# Shematic.net
KiCad netlist of a schematic drawn in Altium Designer
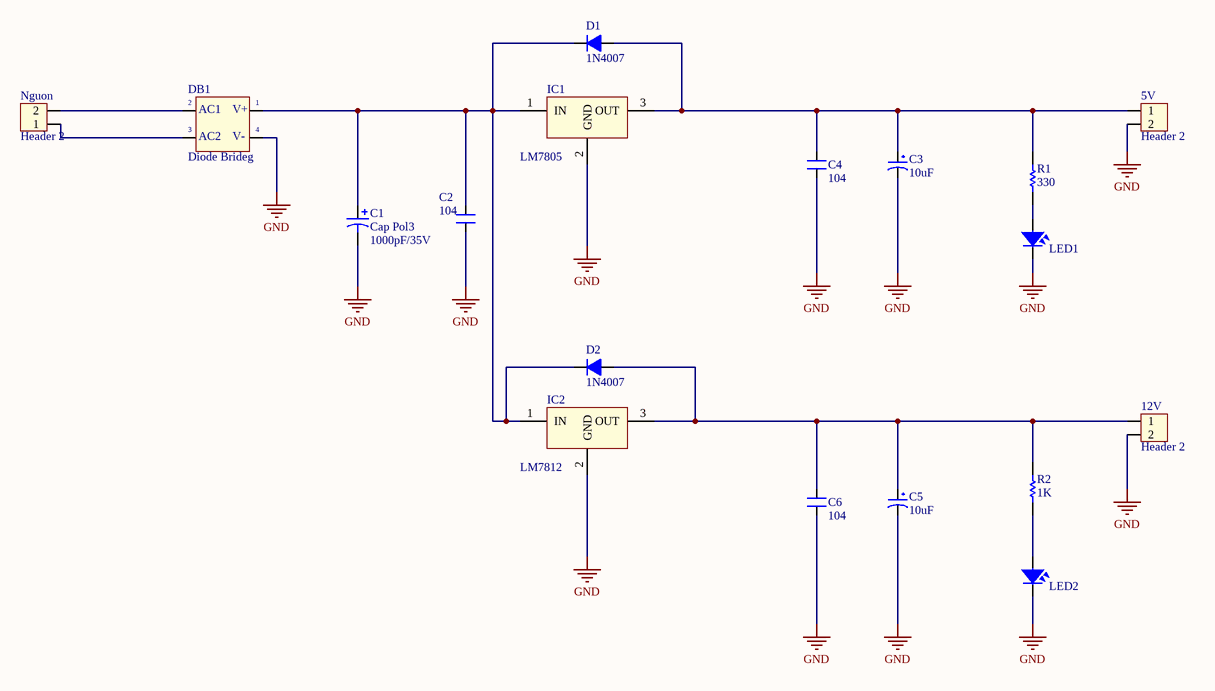
[diagram p0: Shematic.SchDoc]

(export (version "E")
  (design (tool "Eeschema 10.0.6"))
  (components
    (comp (ref "5V")
      (value "Header 2")
      (footprint "HED2")
      (description "Header 2 (Green)")
      (libsource (lib "syhaunguyen") (part "Hed2"))
    )
    (comp (ref "12V")
      (value "Header 2")
      (footprint "HED2")
      (description "Header 2 (Green)")
      (libsource (lib "syhaunguyen") (part "Hed2"))
    )
    (comp (ref "C1")
      (value "Cap Pol3")
      (footprint "CP2/5")
      (description "Polarized Capacitor (Surface Mount)")
      (fields (field (name "ALTIUM_VALUE") "1000pF/35V") (field (name "PUBLISHER") "Altium Limited"))
      (libsource (lib "syhaunguyen") (part "Cap Pol3_2"))
    )
    (comp (ref "C2")
      (value "104")
      (footprint "CN2")
      (description "Cap np 104 => 105pF")
      (libsource (lib "syhaunguyen") (part "CN2"))
    )
    (comp (ref "C3")
      (value "10uF")
      (footprint "CP1/2")
      (description "Cap P  0,1uF < 22uF , 16 - 50V")
      (libsource (lib "syhaunguyen") (part "CP1"))
    )
    (comp (ref "C4")
      (value "104")
      (footprint "CN2")
      (description "Cap np 104 => 105pF")
      (libsource (lib "syhaunguyen") (part "CN2"))
    )
    (comp (ref "C5")
      (value "10uF")
      (footprint "CP1/2")
      (description "Cap P  0,1uF < 22uF , 16 - 50V")
      (libsource (lib "syhaunguyen") (part "CP1"))
    )
    (comp (ref "C6")
      (value "104")
      (footprint "CN2")
      (description "Cap np 104 => 105pF")
      (libsource (lib "syhaunguyen") (part "CN2"))
    )
    (comp (ref "D1")
      (value "1N4007")
      (footprint "D1A")
      (description "Diode 1A")
      (libsource (lib "syhaunguyen") (part "D1A"))
    )
    (comp (ref "D2")
      (value "1N4007")
      (footprint "D1A")
      (description "Diode 1A")
      (libsource (lib "syhaunguyen") (part "D1A"))
    )
    (comp (ref "DB1")
      (value "Diode Brideg")
      (footprint "CAU 1A")
      (description "Convert AC to DC voltage, 4 pin")
      (libsource (lib "syhaunguyen") (part "DB"))
    )
    (comp (ref "IC1")
      (value "LM7805")
      (footprint "QTO-220")
      (description "On ap +, from + 5 to + 24VDC")
      (libsource (lib "syhaunguyen") (part "LM78xx"))
    )
    (comp (ref "IC2")
      (value "LM7812")
      (footprint "QTO-220")
      (description "On ap +, from + 5 to + 24VDC")
      (libsource (lib "syhaunguyen") (part "LM78xx"))
    )
    (comp (ref "LED1")
      (value "LED")
      (footprint "LED-3")
      (description "LED Single colour Green and Red")
      (libsource (lib "syhaunguyen") (part "LED"))
    )
    (comp (ref "LED2")
      (value "LED")
      (footprint "LED-3")
      (description "LED Single colour Green and Red")
      (libsource (lib "syhaunguyen") (part "LED"))
    )
    (comp (ref "Nguon")
      (value "Header 2")
      (footprint "HED2")
      (description "Header 2 (Green)")
      (libsource (lib "") (part "Hed2_1"))
    )
    (comp (ref "R1")
      (value "330")
      (footprint "R1/4W")
      (description "Resistor")
      (fields
        (field (name "MANUFACTURER") "Generic Components")
        (field (name "Comment") "Res1")
        (field (name "PUBLISHER") "Altium Hobart Technology Centre")
      )
      (libsource (lib "syhaunguyen") (part "Res1_1"))
    )
    (comp (ref "R2")
      (value "1K")
      (footprint "R1/4W")
      (description "Resistor")
      (fields
        (field (name "MANUFACTURER") "Generic Components")
        (field (name "Comment") "Res1")
        (field (name "PUBLISHER") "Altium Hobart Technology Centre")
      )
      (libsource (lib "syhaunguyen") (part "Res1_1"))
    )
  )
  (nets
    (net (code "1") (name "GND") (class "Default")
      (node (ref "12V") (pin "2") (pinfunction "2_2") (pintype "passive"))
      (node (ref "5V") (pin "2") (pinfunction "2_2") (pintype "passive"))
      (node (ref "C1") (pin "2") (pinfunction "2_2") (pintype "passive"))
      (node (ref "C2") (pin "1") (pinfunction "1_1") (pintype "passive"))
      (node (ref "C3") (pin "2") (pinfunction "2_2") (pintype "passive"))
      (node (ref "C4") (pin "1") (pinfunction "1_1") (pintype "passive"))
      (node (ref "C5") (pin "2") (pinfunction "2_2") (pintype "passive"))
      (node (ref "C6") (pin "1") (pinfunction "1_1") (pintype "passive"))
      (node (ref "DB1") (pin "4") (pinfunction "-V_OUT_4") (pintype "passive"))
      (node (ref "IC1") (pin "2") (pinfunction "GND_2") (pintype "passive"))
      (node (ref "IC2") (pin "2") (pinfunction "GND_2") (pintype "passive"))
      (node (ref "LED1") (pin "2") (pinfunction "2_2") (pintype "passive"))
      (node (ref "LED2") (pin "2") (pinfunction "2_2") (pintype "passive"))
    )
    (net (code "2") (name "Net-(D1-A)") (class "Default")
      (node (ref "5V") (pin "1") (pinfunction "1_1") (pintype "passive"))
      (node (ref "C3") (pin "1") (pinfunction "1_1") (pintype "passive"))
      (node (ref "C4") (pin "2") (pinfunction "2_2") (pintype "passive"))
      (node (ref "D1") (pin "1") (pinfunction "A_1") (pintype "passive"))
      (node (ref "IC1") (pin "3") (pinfunction "OUT_3") (pintype "passive"))
      (node (ref "R1") (pin "2") (pinfunction "2_2") (pintype "passive"))
    )
    (net (code "3") (name "Net-(D1-K)") (class "Default")
      (node (ref "C1") (pin "1") (pinfunction "1_1") (pintype "passive"))
      (node (ref "C2") (pin "2") (pinfunction "2_2") (pintype "passive"))
      (node (ref "D1") (pin "2") (pinfunction "K_2") (pintype "passive"))
      (node (ref "D2") (pin "2") (pinfunction "K_2") (pintype "passive"))
      (node (ref "DB1") (pin "1") (pinfunction "+V_OUT_1") (pintype "passive"))
      (node (ref "IC1") (pin "1") (pinfunction "IN_1") (pintype "passive"))
      (node (ref "IC2") (pin "1") (pinfunction "IN_1") (pintype "passive"))
    )
    (net (code "4") (name "Net-(D2-A)") (class "Default")
      (node (ref "12V") (pin "1") (pinfunction "1_1") (pintype "passive"))
      (node (ref "C5") (pin "1") (pinfunction "1_1") (pintype "passive"))
      (node (ref "C6") (pin "2") (pinfunction "2_2") (pintype "passive"))
      (node (ref "D2") (pin "1") (pinfunction "A_1") (pintype "passive"))
      (node (ref "IC2") (pin "3") (pinfunction "OUT_3") (pintype "passive"))
      (node (ref "R2") (pin "2") (pinfunction "2_2") (pintype "passive"))
    )
    (net (code "5") (name "Net-(DB1-AC1)") (class "Default")
      (node (ref "DB1") (pin "2") (pinfunction "AC1_2") (pintype "passive"))
      (node (ref "Nguon") (pin "2") (pinfunction "2_2") (pintype "passive"))
    )
    (net (code "6") (name "Net-(DB1-AC2)") (class "Default")
      (node (ref "DB1") (pin "3") (pinfunction "AC2_3") (pintype "passive"))
      (node (ref "Nguon") (pin "1") (pinfunction "1_1") (pintype "passive"))
    )
    (net (code "7") (name "Net-(LED1-Pad1)") (class "Default")
      (node (ref "LED1") (pin "1") (pinfunction "1_1") (pintype "passive"))
      (node (ref "R1") (pin "1") (pinfunction "1_1") (pintype "passive"))
    )
    (net (code "8") (name "Net-(LED2-Pad1)") (class "Default")
      (node (ref "LED2") (pin "1") (pinfunction "1_1") (pintype "passive"))
      (node (ref "R2") (pin "1") (pinfunction "1_1") (pintype "passive"))
    )
  )
)
